# Braking.net
KiCad netlist of a schematic drawn in Altium Designer
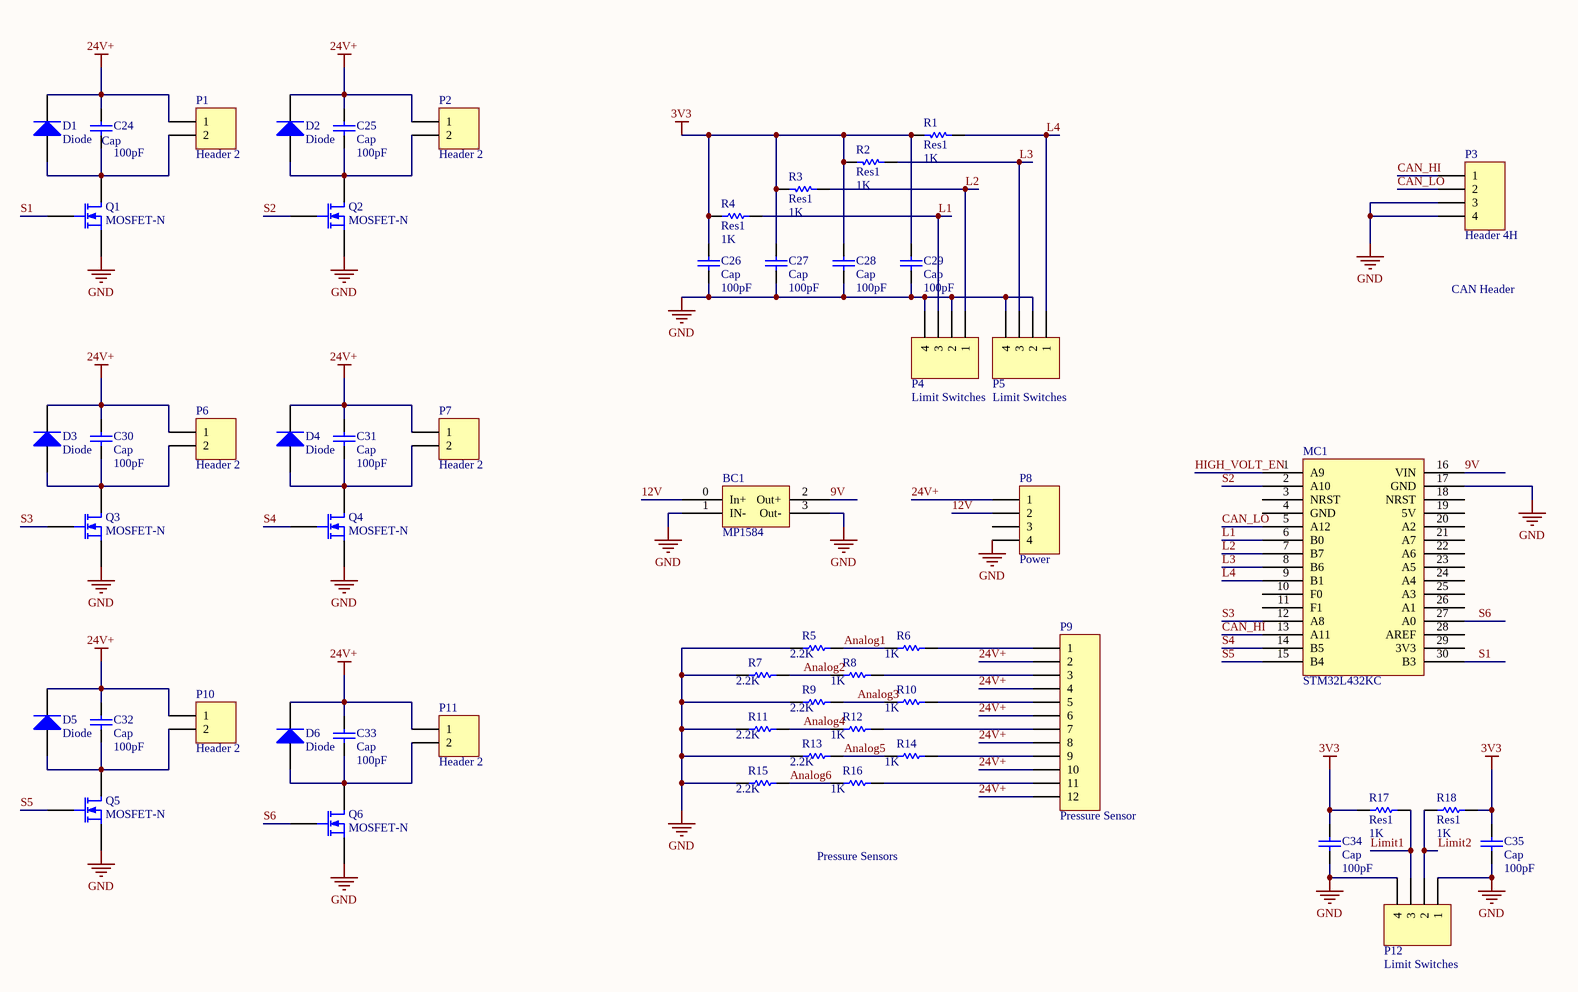
[diagram p0: Braking.SchDoc]

(export (version "E")
  (design (tool "Eeschema 10.0.6"))
  (components
    (comp (ref "BC1") (value "MP1584") (libsource (lib "Pod3") (part "MP1584")))
    (comp (ref "C24")
      (value "Cap")
      (footprint "RAD-0.3")
      (description "Capacitor")
      (fields (field (name "ALTIUM_VALUE") "100pF") (field (name "PUBLISHER") "Altium Limited"))
      (libsource (lib "Miscellaneous Devices") (part "Cap"))
    )
    (comp (ref "C25")
      (value "Cap")
      (footprint "RAD-0.3")
      (description "Capacitor")
      (fields (field (name "ALTIUM_VALUE") "100pF") (field (name "PUBLISHER") "Altium Limited"))
      (libsource (lib "Miscellaneous Devices") (part "Cap"))
    )
    (comp (ref "C26")
      (value "Cap")
      (footprint "RAD-0.3")
      (description "Capacitor")
      (fields (field (name "ALTIUM_VALUE") "100pF") (field (name "PUBLISHER") "Altium Limited"))
      (libsource (lib "Miscellaneous Devices") (part "Cap"))
    )
    (comp (ref "C27")
      (value "Cap")
      (footprint "RAD-0.3")
      (description "Capacitor")
      (fields (field (name "ALTIUM_VALUE") "100pF") (field (name "PUBLISHER") "Altium Limited"))
      (libsource (lib "Miscellaneous Devices") (part "Cap"))
    )
    (comp (ref "C28")
      (value "Cap")
      (footprint "RAD-0.3")
      (description "Capacitor")
      (fields (field (name "ALTIUM_VALUE") "100pF") (field (name "PUBLISHER") "Altium Limited"))
      (libsource (lib "Miscellaneous Devices") (part "Cap"))
    )
    (comp (ref "C29")
      (value "Cap")
      (footprint "RAD-0.3")
      (description "Capacitor")
      (fields (field (name "ALTIUM_VALUE") "100pF") (field (name "PUBLISHER") "Altium Limited"))
      (libsource (lib "Miscellaneous Devices") (part "Cap"))
    )
    (comp (ref "C30")
      (value "Cap")
      (footprint "RAD-0.3")
      (description "Capacitor")
      (fields (field (name "ALTIUM_VALUE") "100pF") (field (name "PUBLISHER") "Altium Limited"))
      (libsource (lib "Miscellaneous Devices") (part "Cap"))
    )
    (comp (ref "C31")
      (value "Cap")
      (footprint "RAD-0.3")
      (description "Capacitor")
      (fields (field (name "ALTIUM_VALUE") "100pF") (field (name "PUBLISHER") "Altium Limited"))
      (libsource (lib "Miscellaneous Devices") (part "Cap"))
    )
    (comp (ref "C32")
      (value "Cap")
      (footprint "RAD-0.3")
      (description "Capacitor")
      (fields (field (name "ALTIUM_VALUE") "100pF") (field (name "PUBLISHER") "Altium Limited"))
      (libsource (lib "Miscellaneous Devices") (part "Cap"))
    )
    (comp (ref "C33")
      (value "Cap")
      (footprint "RAD-0.3")
      (description "Capacitor")
      (fields (field (name "ALTIUM_VALUE") "100pF") (field (name "PUBLISHER") "Altium Limited"))
      (libsource (lib "Miscellaneous Devices") (part "Cap"))
    )
    (comp (ref "C34")
      (value "Cap")
      (footprint "RAD-0.3")
      (description "Capacitor")
      (fields (field (name "ALTIUM_VALUE") "100pF") (field (name "PUBLISHER") "Altium Limited"))
      (libsource (lib "Miscellaneous Devices") (part "Cap"))
    )
    (comp (ref "C35")
      (value "Cap")
      (footprint "RAD-0.3")
      (description "Capacitor")
      (fields (field (name "ALTIUM_VALUE") "100pF") (field (name "PUBLISHER") "Altium Limited"))
      (libsource (lib "Miscellaneous Devices") (part "Cap"))
    )
    (comp (ref "D1")
      (value "Diode")
      (footprint "SMC")
      (description "Default Diode")
      (fields (field (name "PUBLISHER") "Altium Limited"))
      (libsource (lib "Miscellaneous Devices") (part "Diode"))
    )
    (comp (ref "D2")
      (value "Diode")
      (footprint "SMC")
      (description "Default Diode")
      (fields (field (name "PUBLISHER") "Altium Limited"))
      (libsource (lib "Miscellaneous Devices") (part "Diode"))
    )
    (comp (ref "D3")
      (value "Diode")
      (footprint "SMC")
      (description "Default Diode")
      (fields (field (name "PUBLISHER") "Altium Limited"))
      (libsource (lib "Miscellaneous Devices") (part "Diode"))
    )
    (comp (ref "D4")
      (value "Diode")
      (footprint "SMC")
      (description "Default Diode")
      (fields (field (name "PUBLISHER") "Altium Limited"))
      (libsource (lib "Miscellaneous Devices") (part "Diode"))
    )
    (comp (ref "D5")
      (value "Diode")
      (footprint "SMC")
      (description "Default Diode")
      (fields (field (name "PUBLISHER") "Altium Limited"))
      (libsource (lib "Miscellaneous Devices") (part "Diode"))
    )
    (comp (ref "D6")
      (value "Diode")
      (footprint "SMC")
      (description "Default Diode")
      (fields (field (name "PUBLISHER") "Altium Limited"))
      (libsource (lib "Miscellaneous Devices") (part "Diode"))
    )
    (comp (ref "MC1") (value "STM32L432KC") (libsource (lib "Pod3") (part "STMF303K8")))
    (comp (ref "P1")
      (value "Header 2")
      (footprint "HDR1X2")
      (description "Header, 2-Pin")
      (fields (field (name "PUBLISHER") "Altium Limited"))
      (libsource (lib "Miscellaneous Connectors") (part "Header 2"))
    )
    (comp (ref "P2")
      (value "Header 2")
      (footprint "HDR1X2")
      (description "Header, 2-Pin")
      (fields (field (name "PUBLISHER") "Altium Limited"))
      (libsource (lib "Miscellaneous Connectors") (part "Header 2"))
    )
    (comp (ref "P3")
      (value "Header 4H")
      (footprint "HDR1X4H")
      (description "Header, 4-Pin, Right Angle")
      (fields (field (name "PUBLISHER") "Altium Limited"))
      (libsource (lib "Miscellaneous Connectors") (part "Header 4H"))
    )
    (comp (ref "P4")
      (value "Limit Switches")
      (footprint "HDR1X4")
      (description "Header, 4-Pin")
      (fields (field (name "PUBLISHER") "Altium Limited"))
      (libsource (lib "Miscellaneous Connectors") (part "Header 4"))
    )
    (comp (ref "P5")
      (value "Limit Switches")
      (footprint "HDR1X4")
      (description "Header, 4-Pin")
      (fields (field (name "PUBLISHER") "Altium Limited"))
      (libsource (lib "Miscellaneous Connectors") (part "Header 4"))
    )
    (comp (ref "P6")
      (value "Header 2")
      (footprint "HDR1X2")
      (description "Header, 2-Pin")
      (fields (field (name "PUBLISHER") "Altium Limited"))
      (libsource (lib "Miscellaneous Connectors") (part "Header 2"))
    )
    (comp (ref "P7")
      (value "Header 2")
      (footprint "HDR1X2")
      (description "Header, 2-Pin")
      (fields (field (name "PUBLISHER") "Altium Limited"))
      (libsource (lib "Miscellaneous Connectors") (part "Header 2"))
    )
    (comp (ref "P8")
      (value "Power")
      (footprint "HDR1X4")
      (description "Header, 4-Pin")
      (fields (field (name "PUBLISHER") "Altium Limited"))
      (libsource (lib "") (part "Header 4_1"))
    )
    (comp (ref "P9")
      (value "Pressure Sensor")
      (footprint "HDR1X12")
      (description "Header, 12-Pin")
      (fields (field (name "PUBLISHER") "Altium Limited"))
      (libsource (lib "Miscellaneous Connectors") (part "Header 12"))
    )
    (comp (ref "P10")
      (value "Header 2")
      (footprint "HDR1X2")
      (description "Header, 2-Pin")
      (fields (field (name "PUBLISHER") "Altium Limited"))
      (libsource (lib "Miscellaneous Connectors") (part "Header 2"))
    )
    (comp (ref "P11")
      (value "Header 2")
      (footprint "HDR1X2")
      (description "Header, 2-Pin")
      (fields (field (name "PUBLISHER") "Altium Limited"))
      (libsource (lib "Miscellaneous Connectors") (part "Header 2"))
    )
    (comp (ref "P12")
      (value "Limit Switches")
      (footprint "HDR1X4")
      (description "Header, 4-Pin")
      (fields (field (name "PUBLISHER") "Altium Limited"))
      (libsource (lib "Miscellaneous Connectors") (part "Header 4"))
    )
    (comp (ref "Q1")
      (value "MOSFET-N")
      (footprint "E3")
      (description "N-Channel MOSFET")
      (fields (field (name "PUBLISHER") "Altium Limited"))
      (libsource (lib "Miscellaneous Devices") (part "MOSFET-N"))
    )
    (comp (ref "Q2")
      (value "MOSFET-N")
      (footprint "E3")
      (description "N-Channel MOSFET")
      (fields (field (name "PUBLISHER") "Altium Limited"))
      (libsource (lib "Miscellaneous Devices") (part "MOSFET-N"))
    )
    (comp (ref "Q3")
      (value "MOSFET-N")
      (footprint "E3")
      (description "N-Channel MOSFET")
      (fields (field (name "PUBLISHER") "Altium Limited"))
      (libsource (lib "Miscellaneous Devices") (part "MOSFET-N"))
    )
    (comp (ref "Q4")
      (value "MOSFET-N")
      (footprint "E3")
      (description "N-Channel MOSFET")
      (fields (field (name "PUBLISHER") "Altium Limited"))
      (libsource (lib "Miscellaneous Devices") (part "MOSFET-N"))
    )
    (comp (ref "Q5")
      (value "MOSFET-N")
      (footprint "E3")
      (description "N-Channel MOSFET")
      (fields (field (name "PUBLISHER") "Altium Limited"))
      (libsource (lib "Miscellaneous Devices") (part "MOSFET-N"))
    )
    (comp (ref "Q6")
      (value "MOSFET-N")
      (footprint "E3")
      (description "N-Channel MOSFET")
      (fields (field (name "PUBLISHER") "Altium Limited"))
      (libsource (lib "Miscellaneous Devices") (part "MOSFET-N"))
    )
    (comp (ref "R1")
      (value "Res1")
      (footprint "AXIAL-0.3")
      (description "Resistor")
      (fields (field (name "ALTIUM_VALUE") "1K") (field (name "PUBLISHER") "Altium Limited"))
      (libsource (lib "Miscellaneous Devices") (part "Res1"))
    )
    (comp (ref "R2")
      (value "Res1")
      (footprint "AXIAL-0.3")
      (description "Resistor")
      (fields (field (name "ALTIUM_VALUE") "1K") (field (name "PUBLISHER") "Altium Limited"))
      (libsource (lib "Miscellaneous Devices") (part "Res1"))
    )
    (comp (ref "R3")
      (value "Res1")
      (footprint "AXIAL-0.3")
      (description "Resistor")
      (fields (field (name "ALTIUM_VALUE") "1K") (field (name "PUBLISHER") "Altium Limited"))
      (libsource (lib "Miscellaneous Devices") (part "Res1"))
    )
    (comp (ref "R4")
      (value "Res1")
      (footprint "AXIAL-0.3")
      (description "Resistor")
      (fields (field (name "ALTIUM_VALUE") "1K") (field (name "PUBLISHER") "Altium Limited"))
      (libsource (lib "Miscellaneous Devices") (part "Res1"))
    )
    (comp (ref "R5")
      (value "2.2K")
      (footprint "AXIAL-0.3")
      (description "Resistor")
      (fields (field (name "Comment") "Res1") (field (name "PUBLISHER") "Altium Limited"))
      (libsource (lib "Miscellaneous Devices") (part "Res1"))
    )
    (comp (ref "R6")
      (value "1K")
      (footprint "AXIAL-0.3")
      (description "Resistor")
      (fields (field (name "Comment") "Res1") (field (name "PUBLISHER") "Altium Limited"))
      (libsource (lib "Miscellaneous Devices") (part "Res1"))
    )
    (comp (ref "R7")
      (value "2.2K")
      (footprint "AXIAL-0.3")
      (description "Resistor")
      (fields (field (name "Comment") "Res1") (field (name "PUBLISHER") "Altium Limited"))
      (libsource (lib "Miscellaneous Devices") (part "Res1"))
    )
    (comp (ref "R8")
      (value "1K")
      (footprint "AXIAL-0.3")
      (description "Resistor")
      (fields (field (name "Comment") "Res1") (field (name "PUBLISHER") "Altium Limited"))
      (libsource (lib "Miscellaneous Devices") (part "Res1"))
    )
    (comp (ref "R9")
      (value "2.2K")
      (footprint "AXIAL-0.3")
      (description "Resistor")
      (fields (field (name "Comment") "Res1") (field (name "PUBLISHER") "Altium Limited"))
      (libsource (lib "Miscellaneous Devices") (part "Res1"))
    )
    (comp (ref "R10")
      (value "1K")
      (footprint "AXIAL-0.3")
      (description "Resistor")
      (fields (field (name "Comment") "Res1") (field (name "PUBLISHER") "Altium Limited"))
      (libsource (lib "Miscellaneous Devices") (part "Res1"))
    )
    (comp (ref "R11")
      (value "2.2K")
      (footprint "AXIAL-0.3")
      (description "Resistor")
      (fields (field (name "Comment") "Res1") (field (name "PUBLISHER") "Altium Limited"))
      (libsource (lib "Miscellaneous Devices") (part "Res1"))
    )
    (comp (ref "R12")
      (value "1K")
      (footprint "AXIAL-0.3")
      (description "Resistor")
      (fields (field (name "Comment") "Res1") (field (name "PUBLISHER") "Altium Limited"))
      (libsource (lib "Miscellaneous Devices") (part "Res1"))
    )
    (comp (ref "R13")
      (value "2.2K")
      (footprint "AXIAL-0.3")
      (description "Resistor")
      (fields (field (name "Comment") "Res1") (field (name "PUBLISHER") "Altium Limited"))
      (libsource (lib "Miscellaneous Devices") (part "Res1"))
    )
    (comp (ref "R14")
      (value "1K")
      (footprint "AXIAL-0.3")
      (description "Resistor")
      (fields (field (name "Comment") "Res1") (field (name "PUBLISHER") "Altium Limited"))
      (libsource (lib "Miscellaneous Devices") (part "Res1"))
    )
    (comp (ref "R15")
      (value "2.2K")
      (footprint "AXIAL-0.3")
      (description "Resistor")
      (fields (field (name "Comment") "Res1") (field (name "PUBLISHER") "Altium Limited"))
      (libsource (lib "Miscellaneous Devices") (part "Res1"))
    )
    (comp (ref "R16")
      (value "1K")
      (footprint "AXIAL-0.3")
      (description "Resistor")
      (fields (field (name "Comment") "Res1") (field (name "PUBLISHER") "Altium Limited"))
      (libsource (lib "Miscellaneous Devices") (part "Res1"))
    )
    (comp (ref "R17")
      (value "Res1")
      (footprint "AXIAL-0.3")
      (description "Resistor")
      (fields (field (name "ALTIUM_VALUE") "1K") (field (name "PUBLISHER") "Altium Limited"))
      (libsource (lib "Miscellaneous Devices") (part "Res1"))
    )
    (comp (ref "R18")
      (value "Res1")
      (footprint "AXIAL-0.3")
      (description "Resistor")
      (fields (field (name "ALTIUM_VALUE") "1K") (field (name "PUBLISHER") "Altium Limited"))
      (libsource (lib "Miscellaneous Devices") (part "Res1"))
    )
  )
  (nets
    (net (code "1") (name "/9V") (class "Default")
      (node (ref "BC1") (pin "2") (pinfunction "Out+_2") (pintype "passive"))
      (node (ref "MC1") (pin "16") (pinfunction "VIN_16") (pintype "passive"))
    )
    (net (code "2") (name "/12V") (class "Default")
      (node (ref "BC1") (pin "0") (pinfunction "In+_0") (pintype "passive"))
      (node (ref "P8") (pin "2") (pinfunction "2_2") (pintype "passive"))
    )
    (net (code "3") (name "/Analog1") (class "Default")
      (node (ref "R5") (pin "2") (pinfunction "2_2") (pintype "passive"))
      (node (ref "R6") (pin "1") (pinfunction "1_1") (pintype "passive"))
    )
    (net (code "4") (name "/Analog2") (class "Default")
      (node (ref "R7") (pin "2") (pinfunction "2_2") (pintype "passive"))
      (node (ref "R8") (pin "1") (pinfunction "1_1") (pintype "passive"))
    )
    (net (code "5") (name "/Analog3") (class "Default")
      (node (ref "R10") (pin "1") (pinfunction "1_1") (pintype "passive"))
      (node (ref "R9") (pin "2") (pinfunction "2_2") (pintype "passive"))
    )
    (net (code "6") (name "/Analog4") (class "Default")
      (node (ref "R11") (pin "2") (pinfunction "2_2") (pintype "passive"))
      (node (ref "R12") (pin "1") (pinfunction "1_1") (pintype "passive"))
    )
    (net (code "7") (name "/Analog5") (class "Default")
      (node (ref "R13") (pin "2") (pinfunction "2_2") (pintype "passive"))
      (node (ref "R14") (pin "1") (pinfunction "1_1") (pintype "passive"))
    )
    (net (code "8") (name "/Analog6") (class "Default")
      (node (ref "R15") (pin "2") (pinfunction "2_2") (pintype "passive"))
      (node (ref "R16") (pin "1") (pinfunction "1_1") (pintype "passive"))
    )
    (net (code "9") (name "/CAN_HI") (class "Default")
      (node (ref "MC1") (pin "13") (pinfunction "A11_13") (pintype "passive"))
      (node (ref "P3") (pin "1") (pinfunction "1_1") (pintype "passive"))
    )
    (net (code "10") (name "/CAN_LO") (class "Default")
      (node (ref "MC1") (pin "5") (pinfunction "A12_5") (pintype "passive"))
      (node (ref "P3") (pin "2") (pinfunction "2_2") (pintype "passive"))
    )
    (net (code "11") (name "/HIGH_VOLT_EN") (class "Default")
      (node (ref "MC1") (pin "1") (pinfunction "A9_1") (pintype "passive"))
    )
    (net (code "12") (name "/L1") (class "Default")
      (node (ref "MC1") (pin "6") (pinfunction "B0_6") (pintype "passive"))
      (node (ref "P4") (pin "3") (pinfunction "3_3") (pintype "passive"))
      (node (ref "R4") (pin "2") (pinfunction "2_2") (pintype "passive"))
    )
    (net (code "13") (name "/L2") (class "Default")
      (node (ref "MC1") (pin "7") (pinfunction "B7_7") (pintype "passive"))
      (node (ref "P4") (pin "1") (pinfunction "1_1") (pintype "passive"))
      (node (ref "R3") (pin "1") (pinfunction "1_1") (pintype "passive"))
    )
    (net (code "14") (name "/L3") (class "Default")
      (node (ref "MC1") (pin "8") (pinfunction "B6_8") (pintype "passive"))
      (node (ref "P5") (pin "3") (pinfunction "3_3") (pintype "passive"))
      (node (ref "R2") (pin "1") (pinfunction "1_1") (pintype "passive"))
    )
    (net (code "15") (name "/L4") (class "Default")
      (node (ref "MC1") (pin "9") (pinfunction "B1_9") (pintype "passive"))
      (node (ref "P5") (pin "1") (pinfunction "1_1") (pintype "passive"))
      (node (ref "R1") (pin "1") (pinfunction "1_1") (pintype "passive"))
    )
    (net (code "16") (name "/Limit1") (class "Default")
      (node (ref "P12") (pin "3") (pinfunction "3_3") (pintype "passive"))
      (node (ref "R17") (pin "2") (pinfunction "2_2") (pintype "passive"))
    )
    (net (code "17") (name "/Limit2") (class "Default")
      (node (ref "P12") (pin "2") (pinfunction "2_2") (pintype "passive"))
      (node (ref "R18") (pin "1") (pinfunction "1_1") (pintype "passive"))
    )
    (net (code "18") (name "/S1") (class "Default")
      (node (ref "MC1") (pin "30") (pinfunction "B3_30") (pintype "passive"))
      (node (ref "Q1") (pin "2") (pinfunction "G_2") (pintype "passive"))
    )
    (net (code "19") (name "/S2") (class "Default")
      (node (ref "MC1") (pin "2") (pinfunction "A10_2") (pintype "passive"))
      (node (ref "Q2") (pin "2") (pinfunction "G_2") (pintype "passive"))
    )
    (net (code "20") (name "/S3") (class "Default")
      (node (ref "MC1") (pin "12") (pinfunction "A8_12") (pintype "passive"))
      (node (ref "Q3") (pin "2") (pinfunction "G_2") (pintype "passive"))
    )
    (net (code "21") (name "/S4") (class "Default")
      (node (ref "MC1") (pin "14") (pinfunction "B5_14") (pintype "passive"))
      (node (ref "Q4") (pin "2") (pinfunction "G_2") (pintype "passive"))
    )
    (net (code "22") (name "/S5") (class "Default")
      (node (ref "MC1") (pin "15") (pinfunction "B4_15") (pintype "passive"))
      (node (ref "Q5") (pin "2") (pinfunction "G_2") (pintype "passive"))
    )
    (net (code "23") (name "/S6") (class "Default")
      (node (ref "MC1") (pin "27") (pinfunction "A0_27") (pintype "passive"))
      (node (ref "Q6") (pin "2") (pinfunction "G_2") (pintype "passive"))
    )
    (net (code "24") (name "3V3") (class "Default")
      (node (ref "C26") (pin "2") (pinfunction "2_2") (pintype "passive"))
      (node (ref "C27") (pin "2") (pinfunction "2_2") (pintype "passive"))
      (node (ref "C28") (pin "2") (pinfunction "2_2") (pintype "passive"))
      (node (ref "C29") (pin "2") (pinfunction "2_2") (pintype "passive"))
      (node (ref "C34") (pin "2") (pinfunction "2_2") (pintype "passive"))
      (node (ref "C35") (pin "2") (pinfunction "2_2") (pintype "passive"))
      (node (ref "R1") (pin "2") (pinfunction "2_2") (pintype "passive"))
      (node (ref "R17") (pin "1") (pinfunction "1_1") (pintype "passive"))
      (node (ref "R18") (pin "2") (pinfunction "2_2") (pintype "passive"))
      (node (ref "R2") (pin "2") (pinfunction "2_2") (pintype "passive"))
      (node (ref "R3") (pin "2") (pinfunction "2_2") (pintype "passive"))
      (node (ref "R4") (pin "1") (pinfunction "1_1") (pintype "passive"))
    )
    (net (code "25") (name "24V+") (class "Default")
      (node (ref "C24") (pin "1") (pinfunction "1_1") (pintype "passive"))
      (node (ref "C25") (pin "1") (pinfunction "1_1") (pintype "passive"))
      (node (ref "C30") (pin "1") (pinfunction "1_1") (pintype "passive"))
      (node (ref "C31") (pin "1") (pinfunction "1_1") (pintype "passive"))
      (node (ref "C32") (pin "1") (pinfunction "1_1") (pintype "passive"))
      (node (ref "C33") (pin "1") (pinfunction "1_1") (pintype "passive"))
      (node (ref "D1") (pin "2") (pinfunction "K_2") (pintype "passive"))
      (node (ref "D2") (pin "2") (pinfunction "K_2") (pintype "passive"))
      (node (ref "D3") (pin "2") (pinfunction "K_2") (pintype "passive"))
      (node (ref "D4") (pin "2") (pinfunction "K_2") (pintype "passive"))
      (node (ref "D5") (pin "2") (pinfunction "K_2") (pintype "passive"))
      (node (ref "D6") (pin "2") (pinfunction "K_2") (pintype "passive"))
      (node (ref "P1") (pin "1") (pinfunction "1_1") (pintype "passive"))
      (node (ref "P10") (pin "1") (pinfunction "1_1") (pintype "passive"))
      (node (ref "P11") (pin "1") (pinfunction "1_1") (pintype "passive"))
      (node (ref "P2") (pin "1") (pinfunction "1_1") (pintype "passive"))
      (node (ref "P6") (pin "1") (pinfunction "1_1") (pintype "passive"))
      (node (ref "P7") (pin "1") (pinfunction "1_1") (pintype "passive"))
      (node (ref "P8") (pin "1") (pinfunction "1_1") (pintype "passive"))
      (node (ref "P9") (pin "10") (pinfunction "10_10") (pintype "passive"))
      (node (ref "P9") (pin "12") (pinfunction "12_12") (pintype "passive"))
      (node (ref "P9") (pin "2") (pinfunction "2_2") (pintype "passive"))
      (node (ref "P9") (pin "4") (pinfunction "4_4") (pintype "passive"))
      (node (ref "P9") (pin "6") (pinfunction "6_6") (pintype "passive"))
      (node (ref "P9") (pin "8") (pinfunction "8_8") (pintype "passive"))
    )
    (net (code "26") (name "GND") (class "Default")
      (node (ref "BC1") (pin "1") (pinfunction "IN-_1") (pintype "passive"))
      (node (ref "BC1") (pin "3") (pinfunction "Out-_3") (pintype "passive"))
      (node (ref "C26") (pin "1") (pinfunction "1_1") (pintype "passive"))
      (node (ref "C27") (pin "1") (pinfunction "1_1") (pintype "passive"))
      (node (ref "C28") (pin "1") (pinfunction "1_1") (pintype "passive"))
      (node (ref "C29") (pin "1") (pinfunction "1_1") (pintype "passive"))
      (node (ref "C34") (pin "1") (pinfunction "1_1") (pintype "passive"))
      (node (ref "C35") (pin "1") (pinfunction "1_1") (pintype "passive"))
      (node (ref "MC1") (pin "17") (pinfunction "GND_17") (pintype "passive"))
      (node (ref "P12") (pin "1") (pinfunction "1_1") (pintype "passive"))
      (node (ref "P12") (pin "4") (pinfunction "4_4") (pintype "passive"))
      (node (ref "P3") (pin "3") (pinfunction "3_3") (pintype "passive"))
      (node (ref "P3") (pin "4") (pinfunction "4_4") (pintype "passive"))
      (node (ref "P4") (pin "2") (pinfunction "2_2") (pintype "passive"))
      (node (ref "P4") (pin "4") (pinfunction "4_4") (pintype "passive"))
      (node (ref "P5") (pin "2") (pinfunction "2_2") (pintype "passive"))
      (node (ref "P5") (pin "4") (pinfunction "4_4") (pintype "passive"))
      (node (ref "P8") (pin "4") (pinfunction "4_4") (pintype "passive"))
      (node (ref "Q1") (pin "3") (pinfunction "S_3") (pintype "passive"))
      (node (ref "Q2") (pin "3") (pinfunction "S_3") (pintype "passive"))
      (node (ref "Q3") (pin "3") (pinfunction "S_3") (pintype "passive"))
      (node (ref "Q4") (pin "3") (pinfunction "S_3") (pintype "passive"))
      (node (ref "Q5") (pin "3") (pinfunction "S_3") (pintype "passive"))
      (node (ref "Q6") (pin "3") (pinfunction "S_3") (pintype "passive"))
      (node (ref "R11") (pin "1") (pinfunction "1_1") (pintype "passive"))
      (node (ref "R13") (pin "1") (pinfunction "1_1") (pintype "passive"))
      (node (ref "R15") (pin "1") (pinfunction "1_1") (pintype "passive"))
      (node (ref "R5") (pin "1") (pinfunction "1_1") (pintype "passive"))
      (node (ref "R7") (pin "1") (pinfunction "1_1") (pintype "passive"))
      (node (ref "R9") (pin "1") (pinfunction "1_1") (pintype "passive"))
    )
    (net (code "27") (name "Net-(D1-A)") (class "Default")
      (node (ref "C24") (pin "2") (pinfunction "2_2") (pintype "passive"))
      (node (ref "D1") (pin "1") (pinfunction "A_1") (pintype "passive"))
      (node (ref "P1") (pin "2") (pinfunction "2_2") (pintype "passive"))
      (node (ref "Q1") (pin "1") (pinfunction "D_1") (pintype "passive"))
    )
    (net (code "28") (name "Net-(D2-A)") (class "Default")
      (node (ref "C25") (pin "2") (pinfunction "2_2") (pintype "passive"))
      (node (ref "D2") (pin "1") (pinfunction "A_1") (pintype "passive"))
      (node (ref "P2") (pin "2") (pinfunction "2_2") (pintype "passive"))
      (node (ref "Q2") (pin "1") (pinfunction "D_1") (pintype "passive"))
    )
    (net (code "29") (name "Net-(D3-A)") (class "Default")
      (node (ref "C30") (pin "2") (pinfunction "2_2") (pintype "passive"))
      (node (ref "D3") (pin "1") (pinfunction "A_1") (pintype "passive"))
      (node (ref "P6") (pin "2") (pinfunction "2_2") (pintype "passive"))
      (node (ref "Q3") (pin "1") (pinfunction "D_1") (pintype "passive"))
    )
    (net (code "30") (name "Net-(D4-A)") (class "Default")
      (node (ref "C31") (pin "2") (pinfunction "2_2") (pintype "passive"))
      (node (ref "D4") (pin "1") (pinfunction "A_1") (pintype "passive"))
      (node (ref "P7") (pin "2") (pinfunction "2_2") (pintype "passive"))
      (node (ref "Q4") (pin "1") (pinfunction "D_1") (pintype "passive"))
    )
    (net (code "31") (name "Net-(D5-A)") (class "Default")
      (node (ref "C32") (pin "2") (pinfunction "2_2") (pintype "passive"))
      (node (ref "D5") (pin "1") (pinfunction "A_1") (pintype "passive"))
      (node (ref "P10") (pin "2") (pinfunction "2_2") (pintype "passive"))
      (node (ref "Q5") (pin "1") (pinfunction "D_1") (pintype "passive"))
    )
    (net (code "32") (name "Net-(D6-A)") (class "Default")
      (node (ref "C33") (pin "2") (pinfunction "2_2") (pintype "passive"))
      (node (ref "D6") (pin "1") (pinfunction "A_1") (pintype "passive"))
      (node (ref "P11") (pin "2") (pinfunction "2_2") (pintype "passive"))
      (node (ref "Q6") (pin "1") (pinfunction "D_1") (pintype "passive"))
    )
    (net (code "33") (name "Net-(P9-Pad1)") (class "Default")
      (node (ref "P9") (pin "1") (pinfunction "1_1") (pintype "passive"))
      (node (ref "R6") (pin "2") (pinfunction "2_2") (pintype "passive"))
    )
    (net (code "34") (name "Net-(P9-Pad3)") (class "Default")
      (node (ref "P9") (pin "3") (pinfunction "3_3") (pintype "passive"))
      (node (ref "R8") (pin "2") (pinfunction "2_2") (pintype "passive"))
    )
    (net (code "35") (name "Net-(P9-Pad5)") (class "Default")
      (node (ref "P9") (pin "5") (pinfunction "5_5") (pintype "passive"))
      (node (ref "R10") (pin "2") (pinfunction "2_2") (pintype "passive"))
    )
    (net (code "36") (name "Net-(P9-Pad7)") (class "Default")
      (node (ref "P9") (pin "7") (pinfunction "7_7") (pintype "passive"))
      (node (ref "R12") (pin "2") (pinfunction "2_2") (pintype "passive"))
    )
    (net (code "37") (name "Net-(P9-Pad9)") (class "Default")
      (node (ref "P9") (pin "9") (pinfunction "9_9") (pintype "passive"))
      (node (ref "R14") (pin "2") (pinfunction "2_2") (pintype "passive"))
    )
    (net (code "38") (name "Net-(P9-Pad11)") (class "Default")
      (node (ref "P9") (pin "11") (pinfunction "11_11") (pintype "passive"))
      (node (ref "R16") (pin "2") (pinfunction "2_2") (pintype "passive"))
    )
    (net (code "39") (name "unconnected-(MC1-3V3-Pad29)") (class "Default")
      (node (ref "MC1") (pin "29") (pinfunction "3V3_29") (pintype "passive"))
    )
    (net (code "40") (name "unconnected-(MC1-5V-Pad19)") (class "Default")
      (node (ref "MC1") (pin "19") (pinfunction "5V_19") (pintype "passive"))
    )
    (net (code "41") (name "unconnected-(MC1-A1-Pad26)") (class "Default")
      (node (ref "MC1") (pin "26") (pinfunction "A1_26") (pintype "passive"))
    )
    (net (code "42") (name "unconnected-(MC1-A2-Pad20)") (class "Default")
      (node (ref "MC1") (pin "20") (pinfunction "A2_20") (pintype "passive"))
    )
    (net (code "43") (name "unconnected-(MC1-A3-Pad25)") (class "Default")
      (node (ref "MC1") (pin "25") (pinfunction "A3_25") (pintype "passive"))
    )
    (net (code "44") (name "unconnected-(MC1-A4-Pad24)") (class "Default")
      (node (ref "MC1") (pin "24") (pinfunction "A4_24") (pintype "passive"))
    )
    (net (code "45") (name "unconnected-(MC1-A5-Pad23)") (class "Default")
      (node (ref "MC1") (pin "23") (pinfunction "A5_23") (pintype "passive"))
    )
    (net (code "46") (name "unconnected-(MC1-A6-Pad22)") (class "Default")
      (node (ref "MC1") (pin "22") (pinfunction "A6_22") (pintype "passive"))
    )
    (net (code "47") (name "unconnected-(MC1-A7-Pad21)") (class "Default")
      (node (ref "MC1") (pin "21") (pinfunction "A7_21") (pintype "passive"))
    )
    (net (code "48") (name "unconnected-(MC1-AREF-Pad28)") (class "Default")
      (node (ref "MC1") (pin "28") (pinfunction "AREF_28") (pintype "passive"))
    )
    (net (code "49") (name "unconnected-(MC1-F0-Pad10)") (class "Default")
      (node (ref "MC1") (pin "10") (pinfunction "F0_10") (pintype "passive"))
    )
    (net (code "50") (name "unconnected-(MC1-F1-Pad11)") (class "Default")
      (node (ref "MC1") (pin "11") (pinfunction "F1_11") (pintype "passive"))
    )
    (net (code "51") (name "unconnected-(MC1-GND-Pad4)") (class "Default")
      (node (ref "MC1") (pin "4") (pinfunction "GND_4") (pintype "passive"))
    )
    (net (code "52") (name "unconnected-(MC1-NRST-Pad3)") (class "Default")
      (node (ref "MC1") (pin "3") (pinfunction "NRST_3") (pintype "passive"))
    )
    (net (code "53") (name "unconnected-(MC1-NRST-Pad18)") (class "Default")
      (node (ref "MC1") (pin "18") (pinfunction "NRST_18") (pintype "passive"))
    )
    (net (code "54") (name "unconnected-(P8-Pad3)") (class "Default")
      (node (ref "P8") (pin "3") (pinfunction "3_3") (pintype "passive"))
    )
  )
)
